# Mecabot_schematic.net
KiCad netlist of a schematic drawn in Altium Designer
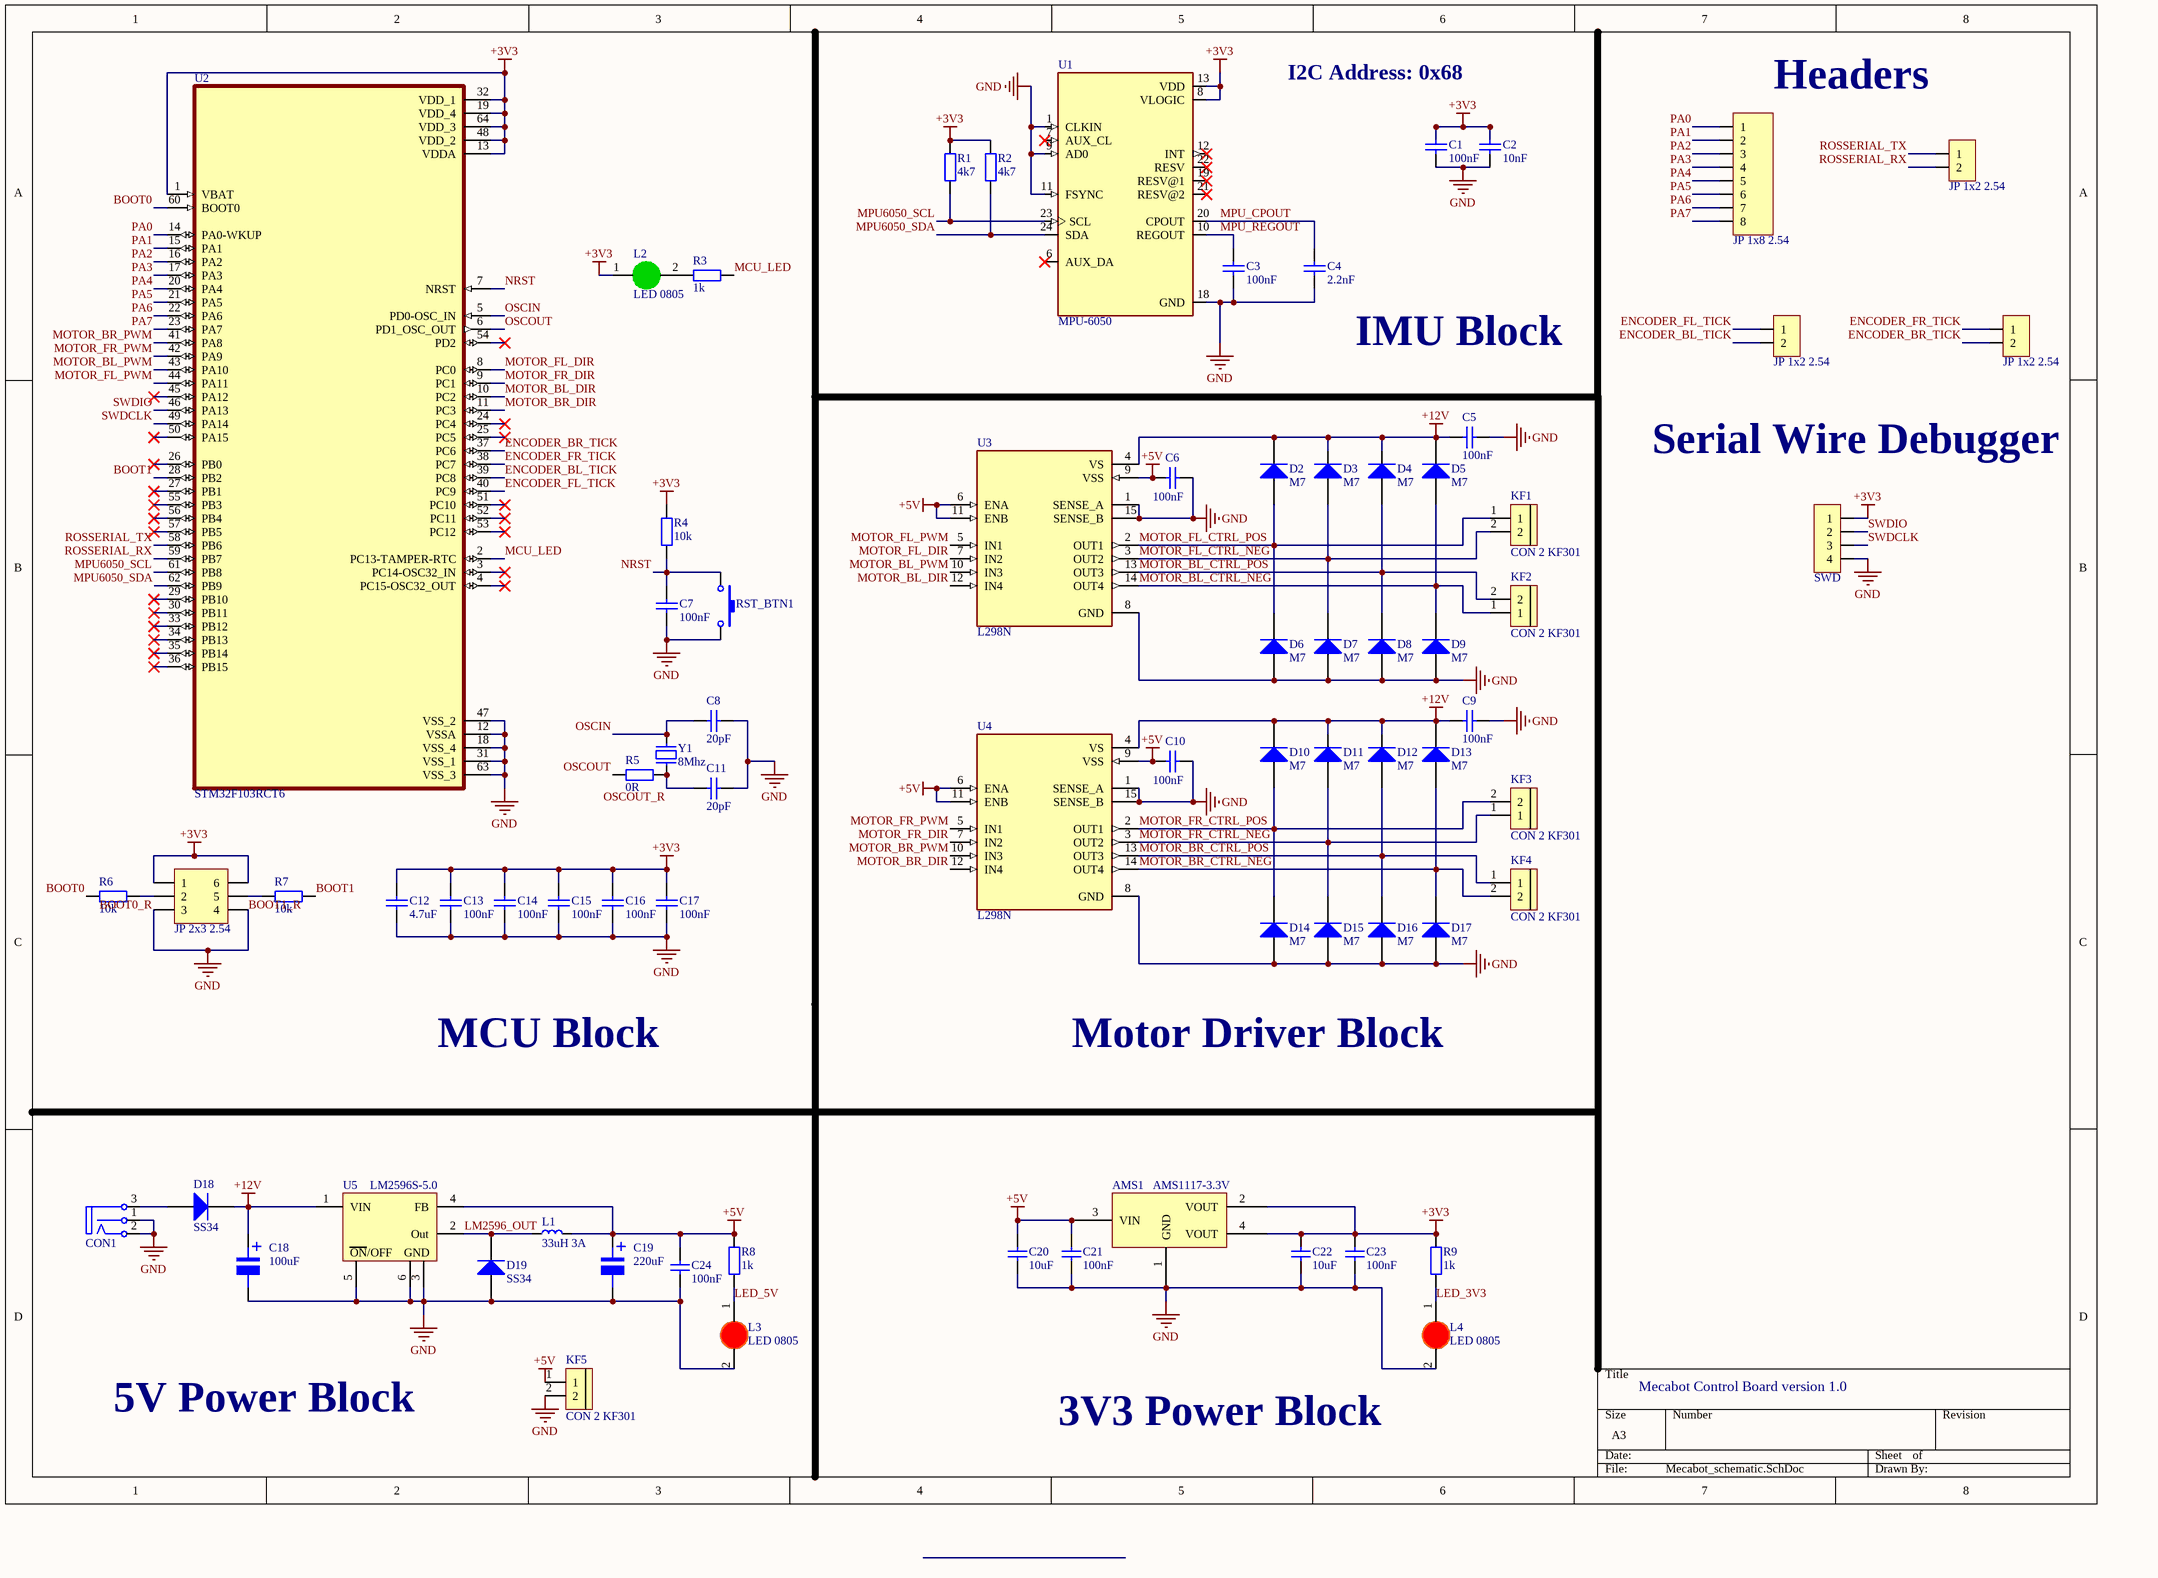
[diagram p0: Mecabot_schematic.SchDoc]

(export (version "E")
  (design (tool "Eeschema 10.0.6"))
  (components
    (comp (ref "AMS1")
      (value "AMS1117-3.3V")
      (footprint "SOT223")
      (description "Dán")
      (libsource (lib "Altium_Lib_by_KhueNguyenCreator") (part "AMS1117 SMD"))
    )
    (comp (ref "C1")
      (value "100nF")
      (footprint "tu 0603")
      (description "Dán")
      (libsource (lib "Altium_Lib_by_KhueNguyenCreator") (part "Tu 0603 104 50V 10%"))
    )
    (comp (ref "C2")
      (value "10nF")
      (footprint "tu 0603")
      (description "Dán")
      (libsource (lib "Altium_Lib_by_KhueNguyenCreator") (part "Tu 0603 103 50V 10%"))
    )
    (comp (ref "C3")
      (value "100nF")
      (footprint "tu 0603")
      (description "Dán")
      (libsource (lib "Altium_Lib_by_KhueNguyenCreator") (part "Tu 0603 104 50V 10%"))
    )
    (comp (ref "C4")
      (value "2.2nF")
      (footprint "tu 0603")
      (description "Dán")
      (libsource (lib "Altium_Lib_by_KhueNguyenCreator") (part "Tu 0603 22pF 50V 10%"))
    )
    (comp (ref "C5")
      (value "100nF")
      (footprint "tu 0603")
      (description "Dán")
      (libsource (lib "Altium_Lib_by_KhueNguyenCreator") (part "Tu 0603 104 50V 10%"))
    )
    (comp (ref "C6")
      (value "100nF")
      (footprint "tu 0603")
      (description "Dán")
      (libsource (lib "Altium_Lib_by_KhueNguyenCreator") (part "Tu 0603 104 50V 10%"))
    )
    (comp (ref "C7")
      (value "100nF")
      (footprint "tu 0603")
      (description "Dán")
      (libsource (lib "Altium_Lib_by_KhueNguyenCreator") (part "Tu 0603 104 50V 10%"))
    )
    (comp (ref "C8")
      (value "20pF")
      (footprint "tu 0603")
      (description "Dán")
      (libsource (lib "Altium_Lib_by_KhueNguyenCreator") (part "Tu 0603 104 50V 10%"))
    )
    (comp (ref "C9")
      (value "100nF")
      (footprint "tu 0603")
      (description "Dán")
      (libsource (lib "Altium_Lib_by_KhueNguyenCreator") (part "Tu 0603 104 50V 10%"))
    )
    (comp (ref "C10")
      (value "100nF")
      (footprint "tu 0603")
      (description "Dán")
      (libsource (lib "Altium_Lib_by_KhueNguyenCreator") (part "Tu 0603 104 50V 10%"))
    )
    (comp (ref "C11")
      (value "20pF")
      (footprint "tu 0603")
      (description "Dán")
      (libsource (lib "Altium_Lib_by_KhueNguyenCreator") (part "Tu 0603 104 50V 10%"))
    )
    (comp (ref "C12")
      (value "4.7uF")
      (footprint "tu 0805")
      (description "Dán")
      (libsource (lib "Altium_Lib_by_KhueNguyenCreator") (part "Tu 0805 475 25V 20%"))
    )
    (comp (ref "C13")
      (value "100nF")
      (footprint "tu 0603")
      (description "Dán")
      (libsource (lib "Altium_Lib_by_KhueNguyenCreator") (part "Tu 0603 104 50V 10%"))
    )
    (comp (ref "C14")
      (value "100nF")
      (footprint "tu 0603")
      (description "Dán")
      (libsource (lib "Altium_Lib_by_KhueNguyenCreator") (part "Tu 0603 104 50V 10%"))
    )
    (comp (ref "C15")
      (value "100nF")
      (footprint "tu 0603")
      (description "Dán")
      (libsource (lib "Altium_Lib_by_KhueNguyenCreator") (part "Tu 0603 104 50V 10%"))
    )
    (comp (ref "C16")
      (value "100nF")
      (footprint "tu 0603")
      (description "Dán")
      (libsource (lib "Altium_Lib_by_KhueNguyenCreator") (part "Tu 0603 104 50V 10%"))
    )
    (comp (ref "C17")
      (value "100nF")
      (footprint "tu 0603")
      (description "Dán")
      (libsource (lib "Altium_Lib_by_KhueNguyenCreator") (part "Tu 0603 104 50V 10%"))
    )
    (comp (ref "C18")
      (value "100uF")
      (footprint "tu nhom 8 (f)")
      (description "Dán")
      (libsource (lib "Altium_Lib_by_KhueNguyenCreator") (part "Tu Nhom 100uF 50V"))
    )
    (comp (ref "C19")
      (value "220uF")
      (footprint "tu nhom 8 (f)")
      (description "Dán")
      (libsource (lib "Altium_Lib_by_KhueNguyenCreator") (part "Tu Nhom 220uF 25V"))
    )
    (comp (ref "C20")
      (value "10uF")
      (footprint "C 0603")
      (description "Capacitor non-pol")
      (libsource (lib "chipfc_altium_libs") (part "Capacitor NP"))
    )
    (comp (ref "C21")
      (value "100nF")
      (footprint "C 0603")
      (description "Capacitor non-pol")
      (libsource (lib "chipfc_altium_libs") (part "Capacitor NP"))
    )
    (comp (ref "C22")
      (value "10uF")
      (footprint "C 0603")
      (description "Capacitor non-pol")
      (libsource (lib "chipfc_altium_libs") (part "Capacitor NP"))
    )
    (comp (ref "C23")
      (value "100nF")
      (footprint "C 0603")
      (description "Capacitor non-pol")
      (libsource (lib "chipfc_altium_libs") (part "Capacitor NP"))
    )
    (comp (ref "C24")
      (value "100nF")
      (footprint "C 0603")
      (description "Capacitor non-pol")
      (libsource (lib "chipfc_altium_libs") (part "Capacitor NP"))
    )
    (comp (ref "CON1")
      (value "CON DC PWR")
      (footprint "CONN/DC/PWR/5.0MM")
      (description "DC input connector")
      (libsource (lib "chipfc_altium_libs") (part "CON DC PWR"))
    )
    (comp (ref "D2")
      (value "M7")
      (footprint "DIODE SMA")
      (description "Dán")
      (libsource (lib "Altium_Lib_by_KhueNguyenCreator") (part "Diode M7 ( 4007 )"))
    )
    (comp (ref "D3")
      (value "M7")
      (footprint "DIODE SMA")
      (description "Dán")
      (libsource (lib "Altium_Lib_by_KhueNguyenCreator") (part "Diode M7 ( 4007 )"))
    )
    (comp (ref "D4")
      (value "M7")
      (footprint "DIODE SMA")
      (description "Dán")
      (libsource (lib "Altium_Lib_by_KhueNguyenCreator") (part "Diode M7 ( 4007 )"))
    )
    (comp (ref "D5")
      (value "M7")
      (footprint "DIODE SMA")
      (description "Dán")
      (libsource (lib "Altium_Lib_by_KhueNguyenCreator") (part "Diode M7 ( 4007 )"))
    )
    (comp (ref "D6")
      (value "M7")
      (footprint "DIODE SMA")
      (description "Dán")
      (libsource (lib "Altium_Lib_by_KhueNguyenCreator") (part "Diode M7 ( 4007 )"))
    )
    (comp (ref "D7")
      (value "M7")
      (footprint "DIODE SMA")
      (description "Dán")
      (libsource (lib "Altium_Lib_by_KhueNguyenCreator") (part "Diode M7 ( 4007 )"))
    )
    (comp (ref "D8")
      (value "M7")
      (footprint "DIODE SMA")
      (description "Dán")
      (libsource (lib "Altium_Lib_by_KhueNguyenCreator") (part "Diode M7 ( 4007 )"))
    )
    (comp (ref "D9")
      (value "M7")
      (footprint "DIODE SMA")
      (description "Dán")
      (libsource (lib "Altium_Lib_by_KhueNguyenCreator") (part "Diode M7 ( 4007 )"))
    )
    (comp (ref "D10")
      (value "M7")
      (footprint "DIODE SMA")
      (description "Dán")
      (libsource (lib "Altium_Lib_by_KhueNguyenCreator") (part "Diode M7 ( 4007 )"))
    )
    (comp (ref "D11")
      (value "M7")
      (footprint "DIODE SMA")
      (description "Dán")
      (libsource (lib "Altium_Lib_by_KhueNguyenCreator") (part "Diode M7 ( 4007 )"))
    )
    (comp (ref "D12")
      (value "M7")
      (footprint "DIODE SMA")
      (description "Dán")
      (libsource (lib "Altium_Lib_by_KhueNguyenCreator") (part "Diode M7 ( 4007 )"))
    )
    (comp (ref "D13")
      (value "M7")
      (footprint "DIODE SMA")
      (description "Dán")
      (libsource (lib "Altium_Lib_by_KhueNguyenCreator") (part "Diode M7 ( 4007 )"))
    )
    (comp (ref "D14")
      (value "M7")
      (footprint "DIODE SMA")
      (description "Dán")
      (libsource (lib "Altium_Lib_by_KhueNguyenCreator") (part "Diode M7 ( 4007 )"))
    )
    (comp (ref "D15")
      (value "M7")
      (footprint "DIODE SMA")
      (description "Dán")
      (libsource (lib "Altium_Lib_by_KhueNguyenCreator") (part "Diode M7 ( 4007 )"))
    )
    (comp (ref "D16")
      (value "M7")
      (footprint "DIODE SMA")
      (description "Dán")
      (libsource (lib "Altium_Lib_by_KhueNguyenCreator") (part "Diode M7 ( 4007 )"))
    )
    (comp (ref "D17")
      (value "M7")
      (footprint "DIODE SMA")
      (description "Dán")
      (libsource (lib "Altium_Lib_by_KhueNguyenCreator") (part "Diode M7 ( 4007 )"))
    )
    (comp (ref "D18")
      (value "SS34")
      (footprint "DIODE SMA")
      (description "Dán")
      (libsource (lib "Altium_Lib_by_KhueNguyenCreator") (part "Diode SS34 ( 1N5822 )"))
    )
    (comp (ref "D19")
      (value "SS34")
      (footprint "DIODE SMA")
      (description "Dán")
      (libsource (lib "Altium_Lib_by_KhueNguyenCreator") (part "Diode SS34 ( 1N5822 )"))
    )
    (comp (ref "JP1")
      (value "JP 1x8 2.54")
      (footprint "JP 1x8 CT")
      (description "Cắm")
      (libsource (lib "Altium_Lib_by_KhueNguyenCreator") (part "JP 1x8 2.54 Cai Thang"))
    )
    (comp (ref "JP2")
      (value "JP 1x2 2.54")
      (footprint "JP 1x2 DC")
      (description "Cắm")
      (libsource (lib "Altium_Lib_by_KhueNguyenCreator") (part "JP 1x2 2.54 Duc Cong"))
    )
    (comp (ref "JP3")
      (value "JP 1x2 2.54")
      (footprint "JP 1x2 DT")
      (description "Cắm")
      (libsource (lib "Altium_Lib_by_KhueNguyenCreator") (part "JP 1x2 2.54 Duc Thang"))
    )
    (comp (ref "JP4")
      (value "JP 1x2 2.54")
      (footprint "JP 1x2 DT")
      (description "Cắm")
      (libsource (lib "Altium_Lib_by_KhueNguyenCreator") (part "JP 1x2 2.54 Duc Thang"))
    )
    (comp (ref "JP5")
      (value "SWD")
      (footprint "JP 1x4 DC")
      (description "Cắm")
      (libsource (lib "Altium_Lib_by_KhueNguyenCreator") (part "JP 1x4 2.54 Duc Cong"))
    )
    (comp (ref "JP6")
      (value "JP 2x3 2.54")
      (footprint "JP 2x3 DT")
      (description "Cắm")
      (libsource (lib "Altium_Lib_by_KhueNguyenCreator") (part "JP 2x3 2.54 Duc Thang"))
    )
    (comp (ref "KF1")
      (value "CON 2 KF301")
      (footprint "Con 2 KF301 5.08")
      (description "Cắm")
      (libsource (lib "") (part "CON 2 KF301_1"))
    )
    (comp (ref "KF2")
      (value "CON 2 KF301")
      (footprint "Con 2 KF301 5.08")
      (description "Cắm")
      (libsource (lib "Altium_Lib_by_KhueNguyenCreator") (part "CON 2 KF301"))
    )
    (comp (ref "KF3")
      (value "CON 2 KF301")
      (footprint "Con 2 KF301 5.08")
      (description "Cắm")
      (libsource (lib "Altium_Lib_by_KhueNguyenCreator") (part "CON 2 KF301"))
    )
    (comp (ref "KF4")
      (value "CON 2 KF301")
      (footprint "Con 2 KF301 5.08")
      (description "Cắm")
      (libsource (lib "") (part "CON 2 KF301_1"))
    )
    (comp (ref "KF5")
      (value "CON 2 KF301")
      (footprint "Con 2 KF301 5.08")
      (description "Cắm")
      (libsource (lib "") (part "CON 2 KF301_1"))
    )
    (comp (ref "L1")
      (value "33uH 3A")
      (footprint "Inductor SMD 12x12x8")
      (description "Inductor")
      (libsource (lib "chipfc_altium_libs") (part "Inductor"))
    )
    (comp (ref "L2")
      (value "LED 0805")
      (footprint "LED-1206-Green")
      (description "Dán")
      (libsource (lib "Altium_Lib_by_KhueNguyenCreator") (part "LED 1206 Xanh La"))
    )
    (comp (ref "L3")
      (value "LED 0805")
      (footprint "LED-1206-Red")
      (description "Dán")
      (libsource (lib "Altium_Lib_by_KhueNguyenCreator") (part "LED 1206 Do"))
    )
    (comp (ref "L4")
      (value "LED 0805")
      (footprint "LED-1206-Red")
      (description "Dán")
      (libsource (lib "Altium_Lib_by_KhueNguyenCreator") (part "LED 1206 Do"))
    )
    (comp (ref "R1")
      (value "4k7")
      (footprint "tro smd 0603")
      (description "Dán")
      (libsource (lib "Altium_Lib_by_KhueNguyenCreator") (part "Tro 0603 1% 0R"))
    )
    (comp (ref "R2")
      (value "4k7")
      (footprint "tro smd 0603")
      (description "Dán")
      (libsource (lib "Altium_Lib_by_KhueNguyenCreator") (part "Tro 0603 1% 0R"))
    )
    (comp (ref "R3")
      (value "1k")
      (footprint "tro smd 0603")
      (description "Dán")
      (libsource (lib "Altium_Lib_by_KhueNguyenCreator") (part "Tro 0603 1% 0R"))
    )
    (comp (ref "R4")
      (value "10k")
      (footprint "tro smd 0603")
      (description "Dán")
      (libsource (lib "Altium_Lib_by_KhueNguyenCreator") (part "Tro 0603 1% 0R"))
    )
    (comp (ref "R5")
      (value "0R")
      (footprint "tro smd 0603")
      (description "Dán")
      (libsource (lib "Altium_Lib_by_KhueNguyenCreator") (part "Tro 0603 1% 0R"))
    )
    (comp (ref "R6")
      (value "10k")
      (footprint "tro smd 0603")
      (description "Dán")
      (libsource (lib "Altium_Lib_by_KhueNguyenCreator") (part "Tro 0603 1% 0R"))
    )
    (comp (ref "R7")
      (value "10k")
      (footprint "tro smd 0603")
      (description "Dán")
      (libsource (lib "Altium_Lib_by_KhueNguyenCreator") (part "Tro 0603 1% 0R"))
    )
    (comp (ref "R8")
      (value "1k")
      (footprint "tro smd 0603")
      (description "Dán")
      (libsource (lib "Altium_Lib_by_KhueNguyenCreator") (part "Tro 0603 1% 0R"))
    )
    (comp (ref "R9")
      (value "1k")
      (footprint "tro smd 0603")
      (description "Dán")
      (libsource (lib "Altium_Lib_by_KhueNguyenCreator") (part "Tro 0603 1% 0R"))
    )
    (comp (ref "RST_BTN1")
      (value "Nut Nhan 2 Chan SMD 3x6x2.5")
      (footprint "Nut Nhan 2 Chan SMD 3x6x2.5")
      (libsource (lib "Altium_Lib_by_KhueNguyenCreator") (part "Nut Nhan 2 Chan SMD 3x6x2.5"))
    )
    (comp (ref "U1")
      (value "MPU-6050")
      (footprint "QFN50P400X400X95-24N")
      (description "MPU-6050 series Accelerometer, Gyroscope, 3 Axis Sensor Evaluation Board")
      (fields (field (name "MF") "TDK InvenSense"))
      (libsource (lib "MPU-6050") (part "MPU-6050"))
    )
    (comp (ref "U2")
      (value "STM32F103RCT6")
      (footprint "QFP50P1200X1200X160-64N")
      (description "ARMÂ® CortexÂ®-M3 STM32F1 Microcontroller IC 32-Bit 72MHz 256KB (256K x 8) FLASH 64-LQFP (10x10)")
      (fields (field (name "MF") "STMicroelectronics"))
      (libsource (lib "STM32F103RCT6") (part "STM32F103RCT6"))
    )
    (comp (ref "U3")
      (value "L298N")
      (footprint "L298N")
      (description "Half Bridge _4_ Driver DC Motors, Relays, Solenoids, Stepper Motors Bipolar 15-Multiwatt")
      (fields (field (name "MF") "STMicroelectronics"))
      (libsource (lib "Altium_Lib_by_KhueNguyenCreator") (part "L298N"))
    )
    (comp (ref "U4")
      (value "L298N")
      (footprint "L298N")
      (description "Half Bridge _4_ Driver DC Motors, Relays, Solenoids, Stepper Motors Bipolar 15-Multiwatt")
      (fields (field (name "MF") "STMicroelectronics"))
      (libsource (lib "Altium_Lib_by_KhueNguyenCreator") (part "L298N"))
    )
    (comp (ref "U5")
      (value "LM2596S-5.0")
      (footprint "TO-263-5")
      (description "Simple Switcher 3A Step-Down Voltage Regulator")
      (libsource (lib "chipfc_altium_libs") (part "LM2596S-5.0"))
    )
    (comp (ref "Y1")
      (value "8Mhz")
      (footprint "Thach Anh 2 chan cam")
      (description "Crystal For all Crystal 2pin.")
      (libsource (lib "Altium_Lib_by_KhueNguyenCreator") (part "Thach Anh 2 chan Cam"))
    )
  )
  (nets
    (net (code "1") (name "+3V3") (class "Default")
      (node (ref "AMS1") (pin "2") (pinfunction "VOUT_2") (pintype "passive"))
      (node (ref "AMS1") (pin "4") (pinfunction "VOUT_4") (pintype "passive"))
      (node (ref "C1") (pin "1") (pinfunction "1_1") (pintype "passive"))
      (node (ref "C12") (pin "1") (pinfunction "1_1") (pintype "passive"))
      (node (ref "C13") (pin "1") (pinfunction "1_1") (pintype "passive"))
      (node (ref "C14") (pin "1") (pinfunction "1_1") (pintype "passive"))
      (node (ref "C15") (pin "1") (pinfunction "1_1") (pintype "passive"))
      (node (ref "C16") (pin "1") (pinfunction "1_1") (pintype "passive"))
      (node (ref "C17") (pin "1") (pinfunction "1_1") (pintype "passive"))
      (node (ref "C2") (pin "1") (pinfunction "1_1") (pintype "passive"))
      (node (ref "C22") (pin "1") (pinfunction "1_1") (pintype "passive"))
      (node (ref "C23") (pin "1") (pinfunction "1_1") (pintype "passive"))
      (node (ref "JP5") (pin "1") (pinfunction "1_1") (pintype "passive"))
      (node (ref "JP6") (pin "1") (pinfunction "1_1") (pintype "passive"))
      (node (ref "JP6") (pin "6") (pinfunction "6_6") (pintype "passive"))
      (node (ref "L2") (pin "1") (pinfunction "A_1") (pintype "passive"))
      (node (ref "R1") (pin "1") (pinfunction "1_1") (pintype "passive"))
      (node (ref "R2") (pin "1") (pinfunction "1_1") (pintype "passive"))
      (node (ref "R4") (pin "1") (pinfunction "1_1") (pintype "passive"))
      (node (ref "R9") (pin "2") (pinfunction "2_2") (pintype "passive"))
      (node (ref "U1") (pin "13") (pinfunction "VDD_13") (pintype "power_in"))
      (node (ref "U1") (pin "8") (pinfunction "VLOGIC_8") (pintype "power_in"))
      (node (ref "U2") (pin "1") (pinfunction "VBAT_1") (pintype "input"))
      (node (ref "U2") (pin "13") (pinfunction "VDDA_13") (pintype "power_in"))
      (node (ref "U2") (pin "19") (pinfunction "VDD_4_19") (pintype "power_in"))
      (node (ref "U2") (pin "32") (pinfunction "VDD_1_32") (pintype "power_in"))
      (node (ref "U2") (pin "48") (pinfunction "VDD_2_48") (pintype "power_in"))
      (node (ref "U2") (pin "64") (pinfunction "VDD_3_64") (pintype "power_in"))
    )
    (net (code "2") (name "+5V") (class "Default")
      (node (ref "AMS1") (pin "3") (pinfunction "VIN_3") (pintype "passive"))
      (node (ref "C10") (pin "1") (pinfunction "1_1") (pintype "passive"))
      (node (ref "C19") (pin "1") (pinfunction "1_1") (pintype "passive"))
      (node (ref "C20") (pin "1") (pinfunction "1_1") (pintype "passive"))
      (node (ref "C21") (pin "1") (pinfunction "1_1") (pintype "passive"))
      (node (ref "C24") (pin "1") (pinfunction "1_1") (pintype "passive"))
      (node (ref "C6") (pin "1") (pinfunction "1_1") (pintype "passive"))
      (node (ref "KF5") (pin "1") (pinfunction "1_1") (pintype "passive"))
      (node (ref "L1") (pin "2") (pinfunction "2_2") (pintype "passive"))
      (node (ref "R8") (pin "2") (pinfunction "2_2") (pintype "passive"))
      (node (ref "U3") (pin "11") (pinfunction "ENB_11") (pintype "input"))
      (node (ref "U3") (pin "6") (pinfunction "ENA_6") (pintype "input"))
      (node (ref "U3") (pin "9") (pinfunction "VSS_9") (pintype "input"))
      (node (ref "U4") (pin "11") (pinfunction "ENB_11") (pintype "input"))
      (node (ref "U4") (pin "6") (pinfunction "ENA_6") (pintype "input"))
      (node (ref "U4") (pin "9") (pinfunction "VSS_9") (pintype "input"))
      (node (ref "U5") (pin "4") (pinfunction "FB_4") (pintype "passive"))
    )
    (net (code "3") (name "+12V") (class "Default")
      (node (ref "C18") (pin "1") (pinfunction "1_1") (pintype "passive"))
      (node (ref "C5") (pin "1") (pinfunction "1_1") (pintype "passive"))
      (node (ref "C9") (pin "1") (pinfunction "1_1") (pintype "passive"))
      (node (ref "D10") (pin "2") (pinfunction "K_2") (pintype "passive"))
      (node (ref "D11") (pin "2") (pinfunction "K_2") (pintype "passive"))
      (node (ref "D12") (pin "2") (pinfunction "K_2") (pintype "passive"))
      (node (ref "D13") (pin "2") (pinfunction "K_2") (pintype "passive"))
      (node (ref "D18") (pin "2") (pinfunction "K_2") (pintype "passive"))
      (node (ref "D2") (pin "2") (pinfunction "K_2") (pintype "passive"))
      (node (ref "D3") (pin "2") (pinfunction "K_2") (pintype "passive"))
      (node (ref "D4") (pin "2") (pinfunction "K_2") (pintype "passive"))
      (node (ref "D5") (pin "2") (pinfunction "K_2") (pintype "passive"))
      (node (ref "U3") (pin "4") (pinfunction "VS_4") (pintype "power_in"))
      (node (ref "U4") (pin "4") (pinfunction "VS_4") (pintype "power_in"))
      (node (ref "U5") (pin "1") (pinfunction "VIN_1") (pintype "passive"))
    )
    (net (code "4") (name "/BOOT0") (class "Default")
      (node (ref "R6") (pin "2") (pinfunction "2_2") (pintype "passive"))
      (node (ref "U2") (pin "60") (pinfunction "BOOT0_60") (pintype "input"))
    )
    (net (code "5") (name "/BOOT0_R") (class "Default")
      (node (ref "JP6") (pin "2") (pinfunction "2_2") (pintype "passive"))
      (node (ref "R6") (pin "1") (pinfunction "1_1") (pintype "passive"))
    )
    (net (code "6") (name "/BOOT1") (class "Default")
      (node (ref "R7") (pin "1") (pinfunction "1_1") (pintype "passive"))
      (node (ref "U2") (pin "28") (pinfunction "PB2_28") (pintype "bidirectional"))
    )
    (net (code "7") (name "/BOOT1_R") (class "Default")
      (node (ref "JP6") (pin "5") (pinfunction "5_5") (pintype "passive"))
      (node (ref "R7") (pin "2") (pinfunction "2_2") (pintype "passive"))
    )
    (net (code "8") (name "/ENCODER_BL_TICK") (class "Default")
      (node (ref "JP3") (pin "2") (pinfunction "2_2") (pintype "passive"))
      (node (ref "U2") (pin "39") (pinfunction "PC8_39") (pintype "bidirectional"))
    )
    (net (code "9") (name "/ENCODER_BR_TICK") (class "Default")
      (node (ref "JP4") (pin "2") (pinfunction "2_2") (pintype "passive"))
      (node (ref "U2") (pin "37") (pinfunction "PC6_37") (pintype "bidirectional"))
    )
    (net (code "10") (name "/ENCODER_FL_TICK") (class "Default")
      (node (ref "JP3") (pin "1") (pinfunction "1_1") (pintype "passive"))
      (node (ref "U2") (pin "40") (pinfunction "PC9_40") (pintype "bidirectional"))
    )
    (net (code "11") (name "/ENCODER_FR_TICK") (class "Default")
      (node (ref "JP4") (pin "1") (pinfunction "1_1") (pintype "passive"))
      (node (ref "U2") (pin "38") (pinfunction "PC7_38") (pintype "bidirectional"))
    )
    (net (code "12") (name "/LED_3V3") (class "Default")
      (node (ref "L4") (pin "1") (pinfunction "A_1") (pintype "passive"))
      (node (ref "R9") (pin "1") (pinfunction "1_1") (pintype "passive"))
    )
    (net (code "13") (name "/LED_5V") (class "Default")
      (node (ref "L3") (pin "1") (pinfunction "A_1") (pintype "passive"))
      (node (ref "R8") (pin "1") (pinfunction "1_1") (pintype "passive"))
    )
    (net (code "14") (name "/LM2596_OUT") (class "Default")
      (node (ref "D19") (pin "2") (pinfunction "K_2") (pintype "passive"))
      (node (ref "L1") (pin "1") (pinfunction "1_1") (pintype "passive"))
      (node (ref "U5") (pin "2") (pinfunction "Out_2") (pintype "passive"))
    )
    (net (code "15") (name "/MCU_LED") (class "Default")
      (node (ref "R3") (pin "1") (pinfunction "1_1") (pintype "passive"))
      (node (ref "U2") (pin "2") (pinfunction "PC13-TAMPER-RTC_2") (pintype "bidirectional"))
    )
    (net (code "16") (name "/MOTOR_BL_CTRL_NEG") (class "Default")
      (node (ref "D5") (pin "1") (pinfunction "A_1") (pintype "passive"))
      (node (ref "D9") (pin "2") (pinfunction "K_2") (pintype "passive"))
      (node (ref "KF2") (pin "1") (pinfunction "1_1") (pintype "passive"))
      (node (ref "U3") (pin "14") (pinfunction "OUT4_14") (pintype "output"))
    )
    (net (code "17") (name "/MOTOR_BL_CTRL_POS") (class "Default")
      (node (ref "D4") (pin "1") (pinfunction "A_1") (pintype "passive"))
      (node (ref "D8") (pin "2") (pinfunction "K_2") (pintype "passive"))
      (node (ref "KF2") (pin "2") (pinfunction "2_2") (pintype "passive"))
      (node (ref "U3") (pin "13") (pinfunction "OUT3_13") (pintype "output"))
    )
    (net (code "18") (name "/MOTOR_BL_DIR") (class "Default")
      (node (ref "U2") (pin "10") (pinfunction "PC2_10") (pintype "bidirectional"))
      (node (ref "U3") (pin "12") (pinfunction "IN4_12") (pintype "input"))
    )
    (net (code "19") (name "/MOTOR_BL_PWM") (class "Default")
      (node (ref "U2") (pin "43") (pinfunction "PA10_43") (pintype "bidirectional"))
      (node (ref "U3") (pin "10") (pinfunction "IN3_10") (pintype "input"))
    )
    (net (code "20") (name "/MOTOR_BR_CTRL_NEG") (class "Default")
      (node (ref "D13") (pin "1") (pinfunction "A_1") (pintype "passive"))
      (node (ref "D17") (pin "2") (pinfunction "K_2") (pintype "passive"))
      (node (ref "KF4") (pin "2") (pinfunction "2_2") (pintype "passive"))
      (node (ref "U4") (pin "14") (pinfunction "OUT4_14") (pintype "output"))
    )
    (net (code "21") (name "/MOTOR_BR_CTRL_POS") (class "Default")
      (node (ref "D12") (pin "1") (pinfunction "A_1") (pintype "passive"))
      (node (ref "D16") (pin "2") (pinfunction "K_2") (pintype "passive"))
      (node (ref "KF4") (pin "1") (pinfunction "1_1") (pintype "passive"))
      (node (ref "U4") (pin "13") (pinfunction "OUT3_13") (pintype "output"))
    )
    (net (code "22") (name "/MOTOR_BR_DIR") (class "Default")
      (node (ref "U2") (pin "11") (pinfunction "PC3_11") (pintype "bidirectional"))
      (node (ref "U4") (pin "12") (pinfunction "IN4_12") (pintype "input"))
    )
    (net (code "23") (name "/MOTOR_BR_PWM") (class "Default")
      (node (ref "U2") (pin "41") (pinfunction "PA8_41") (pintype "bidirectional"))
      (node (ref "U4") (pin "10") (pinfunction "IN3_10") (pintype "input"))
    )
    (net (code "24") (name "/MOTOR_FL_CTRL_NEG") (class "Default")
      (node (ref "D3") (pin "1") (pinfunction "A_1") (pintype "passive"))
      (node (ref "D7") (pin "2") (pinfunction "K_2") (pintype "passive"))
      (node (ref "KF1") (pin "2") (pinfunction "2_2") (pintype "passive"))
      (node (ref "U3") (pin "3") (pinfunction "OUT2_3") (pintype "output"))
    )
    (net (code "25") (name "/MOTOR_FL_CTRL_POS") (class "Default")
      (node (ref "D2") (pin "1") (pinfunction "A_1") (pintype "passive"))
      (node (ref "D6") (pin "2") (pinfunction "K_2") (pintype "passive"))
      (node (ref "KF1") (pin "1") (pinfunction "1_1") (pintype "passive"))
      (node (ref "U3") (pin "2") (pinfunction "OUT1_2") (pintype "output"))
    )
    (net (code "26") (name "/MOTOR_FL_DIR") (class "Default")
      (node (ref "U2") (pin "8") (pinfunction "PC0_8") (pintype "bidirectional"))
      (node (ref "U3") (pin "7") (pinfunction "IN2_7") (pintype "input"))
    )
    (net (code "27") (name "/MOTOR_FL_PWM") (class "Default")
      (node (ref "U2") (pin "44") (pinfunction "PA11_44") (pintype "bidirectional"))
      (node (ref "U3") (pin "5") (pinfunction "IN1_5") (pintype "input"))
    )
    (net (code "28") (name "/MOTOR_FR_CTRL_NEG") (class "Default")
      (node (ref "D11") (pin "1") (pinfunction "A_1") (pintype "passive"))
      (node (ref "D15") (pin "2") (pinfunction "K_2") (pintype "passive"))
      (node (ref "KF3") (pin "1") (pinfunction "1_1") (pintype "passive"))
      (node (ref "U4") (pin "3") (pinfunction "OUT2_3") (pintype "output"))
    )
    (net (code "29") (name "/MOTOR_FR_CTRL_POS") (class "Default")
      (node (ref "D10") (pin "1") (pinfunction "A_1") (pintype "passive"))
      (node (ref "D14") (pin "2") (pinfunction "K_2") (pintype "passive"))
      (node (ref "KF3") (pin "2") (pinfunction "2_2") (pintype "passive"))
      (node (ref "U4") (pin "2") (pinfunction "OUT1_2") (pintype "output"))
    )
    (net (code "30") (name "/MOTOR_FR_DIR") (class "Default")
      (node (ref "U2") (pin "9") (pinfunction "PC1_9") (pintype "bidirectional"))
      (node (ref "U4") (pin "7") (pinfunction "IN2_7") (pintype "input"))
    )
    (net (code "31") (name "/MOTOR_FR_PWM") (class "Default")
      (node (ref "U2") (pin "42") (pinfunction "PA9_42") (pintype "bidirectional"))
      (node (ref "U4") (pin "5") (pinfunction "IN1_5") (pintype "input"))
    )
    (net (code "32") (name "/MPU6050_SCL") (class "Default")
      (node (ref "R1") (pin "2") (pinfunction "2_2") (pintype "passive"))
      (node (ref "U1") (pin "23") (pinfunction "SCL_23") (pintype "input"))
      (node (ref "U2") (pin "61") (pinfunction "PB8_61") (pintype "bidirectional"))
    )
    (net (code "33") (name "/MPU6050_SDA") (class "Default")
      (node (ref "R2") (pin "2") (pinfunction "2_2") (pintype "passive"))
      (node (ref "U1") (pin "24") (pinfunction "SDA_24") (pintype "bidirectional"))
      (node (ref "U2") (pin "62") (pinfunction "PB9_62") (pintype "bidirectional"))
    )
    (net (code "34") (name "/MPU_CPOUT") (class "Default")
      (node (ref "C4") (pin "2") (pinfunction "2_2") (pintype "passive"))
      (node (ref "U1") (pin "20") (pinfunction "CPOUT_20") (pintype "passive"))
    )
    (net (code "35") (name "/MPU_REGOUT") (class "Default")
      (node (ref "C3") (pin "1") (pinfunction "1_1") (pintype "passive"))
      (node (ref "U1") (pin "10") (pinfunction "REGOUT_10") (pintype "passive"))
    )
    (net (code "36") (name "/NRST") (class "Default")
      (node (ref "C7") (pin "1") (pinfunction "1_1") (pintype "passive"))
      (node (ref "R4") (pin "2") (pinfunction "2_2") (pintype "passive"))
      (node (ref "RST_BTN1") (pin "1") (pinfunction "1_1") (pintype "passive"))
      (node (ref "U2") (pin "7") (pinfunction "NRST_7") (pintype "input"))
    )
    (net (code "37") (name "/OSCIN") (class "Default")
      (node (ref "C8") (pin "2") (pinfunction "2_2") (pintype "passive"))
      (node (ref "U2") (pin "5") (pinfunction "PD0-OSC_IN_5") (pintype "input"))
      (node (ref "Y1") (pin "1") (pinfunction "1_1") (pintype "passive"))
    )
    (net (code "38") (name "/OSCOUT") (class "Default")
      (node (ref "R5") (pin "2") (pinfunction "2_2") (pintype "passive"))
      (node (ref "U2") (pin "6") (pinfunction "PD1_OSC_OUT_6") (pintype "output"))
    )
    (net (code "39") (name "/OSCOUT_R") (class "Default")
      (node (ref "C11") (pin "2") (pinfunction "2_2") (pintype "passive"))
      (node (ref "R5") (pin "1") (pinfunction "1_1") (pintype "passive"))
      (node (ref "Y1") (pin "2") (pinfunction "2_2") (pintype "passive"))
    )
    (net (code "40") (name "/PA0") (class "Default")
      (node (ref "JP1") (pin "1") (pinfunction "1_1") (pintype "passive"))
      (node (ref "U2") (pin "14") (pinfunction "PA0-WKUP_14") (pintype "bidirectional"))
    )
    (net (code "41") (name "/PA1") (class "Default")
      (node (ref "JP1") (pin "2") (pinfunction "2_2") (pintype "passive"))
      (node (ref "U2") (pin "15") (pinfunction "PA1_15") (pintype "bidirectional"))
    )
    (net (code "42") (name "/PA2") (class "Default")
      (node (ref "JP1") (pin "3") (pinfunction "3_3") (pintype "passive"))
      (node (ref "U2") (pin "16") (pinfunction "PA2_16") (pintype "bidirectional"))
    )
    (net (code "43") (name "/PA3") (class "Default")
      (node (ref "JP1") (pin "4") (pinfunction "4_4") (pintype "passive"))
      (node (ref "U2") (pin "17") (pinfunction "PA3_17") (pintype "bidirectional"))
    )
    (net (code "44") (name "/PA4") (class "Default")
      (node (ref "JP1") (pin "5") (pinfunction "5_5") (pintype "passive"))
      (node (ref "U2") (pin "20") (pinfunction "PA4_20") (pintype "bidirectional"))
    )
    (net (code "45") (name "/PA5") (class "Default")
      (node (ref "JP1") (pin "6") (pinfunction "6_6") (pintype "passive"))
      (node (ref "U2") (pin "21") (pinfunction "PA5_21") (pintype "bidirectional"))
    )
    (net (code "46") (name "/PA6") (class "Default")
      (node (ref "JP1") (pin "7") (pinfunction "7_7") (pintype "passive"))
      (node (ref "U2") (pin "22") (pinfunction "PA6_22") (pintype "bidirectional"))
    )
    (net (code "47") (name "/PA7") (class "Default")
      (node (ref "JP1") (pin "8") (pinfunction "8_8") (pintype "passive"))
      (node (ref "U2") (pin "23") (pinfunction "PA7_23") (pintype "bidirectional"))
    )
    (net (code "48") (name "/ROSSERIAL_RX") (class "Default")
      (node (ref "JP2") (pin "2") (pinfunction "2_2") (pintype "passive"))
      (node (ref "U2") (pin "59") (pinfunction "PB7_59") (pintype "bidirectional"))
    )
    (net (code "49") (name "/ROSSERIAL_TX") (class "Default")
      (node (ref "JP2") (pin "1") (pinfunction "1_1") (pintype "passive"))
      (node (ref "U2") (pin "58") (pinfunction "PB6_58") (pintype "bidirectional"))
    )
    (net (code "50") (name "/SWDCLK") (class "Default")
      (node (ref "JP5") (pin "3") (pinfunction "3_3") (pintype "passive"))
      (node (ref "U2") (pin "49") (pinfunction "PA14_49") (pintype "bidirectional"))
    )
    (net (code "51") (name "/SWDIO") (class "Default")
      (node (ref "JP5") (pin "2") (pinfunction "2_2") (pintype "passive"))
      (node (ref "U2") (pin "46") (pinfunction "PA13_46") (pintype "bidirectional"))
    )
    (net (code "52") (name "GND") (class "Default")
      (node (ref "AMS1") (pin "1") (pinfunction "GND_1") (pintype "passive"))
      (node (ref "C1") (pin "2") (pinfunction "2_2") (pintype "passive"))
      (node (ref "C10") (pin "2") (pinfunction "2_2") (pintype "passive"))
      (node (ref "C11") (pin "1") (pinfunction "1_1") (pintype "passive"))
      (node (ref "C12") (pin "2") (pinfunction "2_2") (pintype "passive"))
      (node (ref "C13") (pin "2") (pinfunction "2_2") (pintype "passive"))
      (node (ref "C14") (pin "2") (pinfunction "2_2") (pintype "passive"))
      (node (ref "C15") (pin "2") (pinfunction "2_2") (pintype "passive"))
      (node (ref "C16") (pin "2") (pinfunction "2_2") (pintype "passive"))
      (node (ref "C17") (pin "2") (pinfunction "2_2") (pintype "passive"))
      (node (ref "C18") (pin "2") (pinfunction "2_2") (pintype "passive"))
      (node (ref "C19") (pin "2") (pinfunction "2_2") (pintype "passive"))
      (node (ref "C2") (pin "2") (pinfunction "2_2") (pintype "passive"))
      (node (ref "C20") (pin "2") (pinfunction "2_2") (pintype "passive"))
      (node (ref "C21") (pin "2") (pinfunction "2_2") (pintype "passive"))
      (node (ref "C22") (pin "2") (pinfunction "2_2") (pintype "passive"))
      (node (ref "C23") (pin "2") (pinfunction "2_2") (pintype "passive"))
      (node (ref "C24") (pin "2") (pinfunction "2_2") (pintype "passive"))
      (node (ref "C3") (pin "2") (pinfunction "2_2") (pintype "passive"))
      (node (ref "C4") (pin "1") (pinfunction "1_1") (pintype "passive"))
      (node (ref "C5") (pin "2") (pinfunction "2_2") (pintype "passive"))
      (node (ref "C6") (pin "2") (pinfunction "2_2") (pintype "passive"))
      (node (ref "C7") (pin "2") (pinfunction "2_2") (pintype "passive"))
      (node (ref "C8") (pin "1") (pinfunction "1_1") (pintype "passive"))
      (node (ref "C9") (pin "2") (pinfunction "2_2") (pintype "passive"))
      (node (ref "CON1") (pin "1") (pinfunction "S_1") (pintype "power_in"))
      (node (ref "CON1") (pin "2") (pinfunction "T_2") (pintype "passive"))
      (node (ref "D14") (pin "1") (pinfunction "A_1") (pintype "passive"))
      (node (ref "D15") (pin "1") (pinfunction "A_1") (pintype "passive"))
      (node (ref "D16") (pin "1") (pinfunction "A_1") (pintype "passive"))
      (node (ref "D17") (pin "1") (pinfunction "A_1") (pintype "passive"))
      (node (ref "D19") (pin "1") (pinfunction "A_1") (pintype "passive"))
      (node (ref "D6") (pin "1") (pinfunction "A_1") (pintype "passive"))
      (node (ref "D7") (pin "1") (pinfunction "A_1") (pintype "passive"))
      (node (ref "D8") (pin "1") (pinfunction "A_1") (pintype "passive"))
      (node (ref "D9") (pin "1") (pinfunction "A_1") (pintype "passive"))
      (node (ref "JP5") (pin "4") (pinfunction "4_4") (pintype "passive"))
      (node (ref "JP6") (pin "3") (pinfunction "3_3") (pintype "passive"))
      (node (ref "JP6") (pin "4") (pinfunction "4_4") (pintype "passive"))
      (node (ref "KF5") (pin "2") (pinfunction "2_2") (pintype "passive"))
      (node (ref "L3") (pin "2") (pinfunction "K_2") (pintype "passive"))
      (node (ref "L4") (pin "2") (pinfunction "K_2") (pintype "passive"))
      (node (ref "RST_BTN1") (pin "2") (pinfunction "2_2") (pintype "passive"))
      (node (ref "U1") (pin "1") (pinfunction "CLKIN_1") (pintype "input"))
      (node (ref "U1") (pin "11") (pinfunction "FSYNC_11") (pintype "input"))
      (node (ref "U1") (pin "18") (pinfunction "GND_18") (pintype "power_in"))
      (node (ref "U1") (pin "9") (pinfunction "AD0_9") (pintype "input"))
      (node (ref "U2") (pin "12") (pinfunction "VSSA_12") (pintype "power_in"))
      (node (ref "U2") (pin "18") (pinfunction "VSS_4_18") (pintype "power_in"))
      (node (ref "U2") (pin "31") (pinfunction "VSS_1_31") (pintype "power_in"))
      (node (ref "U2") (pin "47") (pinfunction "VSS_2_47") (pintype "power_in"))
      (node (ref "U2") (pin "63") (pinfunction "VSS_3_63") (pintype "power_in"))
      (node (ref "U3") (pin "1") (pinfunction "SENSE_A_1") (pintype "passive"))
      (node (ref "U3") (pin "15") (pinfunction "SENSE_B_15") (pintype "passive"))
      (node (ref "U3") (pin "8") (pinfunction "GND_8") (pintype "power_in"))
      (node (ref "U4") (pin "1") (pinfunction "SENSE_A_1") (pintype "passive"))
      (node (ref "U4") (pin "15") (pinfunction "SENSE_B_15") (pintype "passive"))
      (node (ref "U4") (pin "8") (pinfunction "GND_8") (pintype "power_in"))
      (node (ref "U5") (pin "3") (pinfunction "GND_3") (pintype "passive"))
      (node (ref "U5") (pin "5") (pinfunction "~{ON}/OFF_5") (pintype "passive"))
      (node (ref "U5") (pin "6") (pinfunction "PAD_6") (pintype "passive"))
    )
    (net (code "53") (name "Net-(CON1-TN)") (class "Default")
      (node (ref "CON1") (pin "3") (pinfunction "TN_3") (pintype "passive"))
      (node (ref "D18") (pin "1") (pinfunction "A_1") (pintype "passive"))
    )
    (net (code "54") (name "Net-(L2-K)") (class "Default")
      (node (ref "L2") (pin "2") (pinfunction "K_2") (pintype "passive"))
      (node (ref "R3") (pin "2") (pinfunction "2_2") (pintype "passive"))
    )
    (net (code "55") (name "unconnected-(U1-AUX_CL-Pad7)") (class "Default")
      (node (ref "U1") (pin "7") (pinfunction "AUX_CL_7") (pintype "input+no_connect"))
    )
    (net (code "56") (name "unconnected-(U1-AUX_DA-Pad6)") (class "Default")
      (node (ref "U1") (pin "6") (pinfunction "AUX_DA_6") (pintype "bidirectional+no_connect"))
    )
    (net (code "57") (name "unconnected-(U1-INT-Pad12)") (class "Default")
      (node (ref "U1") (pin "12") (pinfunction "INT_12") (pintype "output+no_connect"))
    )
    (net (code "58") (name "unconnected-(U1-RESV-Pad22)") (class "Default")
      (node (ref "U1") (pin "22") (pinfunction "RESV_22") (pintype "passive+no_connect"))
    )
    (net (code "59") (name "unconnected-(U1-RESV@1-Pad19)") (class "Default")
      (node (ref "U1") (pin "19") (pinfunction "RESV@1_19") (pintype "passive+no_connect"))
    )
    (net (code "60") (name "unconnected-(U1-RESV@2-Pad21)") (class "Default")
      (node (ref "U1") (pin "21") (pinfunction "RESV@2_21") (pintype "passive+no_connect"))
    )
    (net (code "61") (name "unconnected-(U2-PA12-Pad45)") (class "Default")
      (node (ref "U2") (pin "45") (pinfunction "PA12_45") (pintype "bidirectional+no_connect"))
    )
    (net (code "62") (name "unconnected-(U2-PA15-Pad50)") (class "Default")
      (node (ref "U2") (pin "50") (pinfunction "PA15_50") (pintype "bidirectional+no_connect"))
    )
    (net (code "63") (name "unconnected-(U2-PB0-Pad26)") (class "Default")
      (node (ref "U2") (pin "26") (pinfunction "PB0_26") (pintype "bidirectional+no_connect"))
    )
    (net (code "64") (name "unconnected-(U2-PB1-Pad27)") (class "Default")
      (node (ref "U2") (pin "27") (pinfunction "PB1_27") (pintype "bidirectional+no_connect"))
    )
    (net (code "65") (name "unconnected-(U2-PB3-Pad55)") (class "Default")
      (node (ref "U2") (pin "55") (pinfunction "PB3_55") (pintype "bidirectional+no_connect"))
    )
    (net (code "66") (name "unconnected-(U2-PB4-Pad56)") (class "Default")
      (node (ref "U2") (pin "56") (pinfunction "PB4_56") (pintype "bidirectional+no_connect"))
    )
    (net (code "67") (name "unconnected-(U2-PB5-Pad57)") (class "Default")
      (node (ref "U2") (pin "57") (pinfunction "PB5_57") (pintype "bidirectional+no_connect"))
    )
    (net (code "68") (name "unconnected-(U2-PB10-Pad29)") (class "Default")
      (node (ref "U2") (pin "29") (pinfunction "PB10_29") (pintype "bidirectional+no_connect"))
    )
    (net (code "69") (name "unconnected-(U2-PB11-Pad30)") (class "Default")
      (node (ref "U2") (pin "30") (pinfunction "PB11_30") (pintype "bidirectional+no_connect"))
    )
    (net (code "70") (name "unconnected-(U2-PB12-Pad33)") (class "Default")
      (node (ref "U2") (pin "33") (pinfunction "PB12_33") (pintype "bidirectional+no_connect"))
    )
    (net (code "71") (name "unconnected-(U2-PB13-Pad34)") (class "Default")
      (node (ref "U2") (pin "34") (pinfunction "PB13_34") (pintype "bidirectional+no_connect"))
    )
    (net (code "72") (name "unconnected-(U2-PB14-Pad35)") (class "Default")
      (node (ref "U2") (pin "35") (pinfunction "PB14_35") (pintype "bidirectional+no_connect"))
    )
    (net (code "73") (name "unconnected-(U2-PB15-Pad36)") (class "Default")
      (node (ref "U2") (pin "36") (pinfunction "PB15_36") (pintype "bidirectional+no_connect"))
    )
    (net (code "74") (name "unconnected-(U2-PC4-Pad24)") (class "Default")
      (node (ref "U2") (pin "24") (pinfunction "PC4_24") (pintype "bidirectional+no_connect"))
    )
    (net (code "75") (name "unconnected-(U2-PC5-Pad25)") (class "Default")
      (node (ref "U2") (pin "25") (pinfunction "PC5_25") (pintype "bidirectional+no_connect"))
    )
    (net (code "76") (name "unconnected-(U2-PC10-Pad51)") (class "Default")
      (node (ref "U2") (pin "51") (pinfunction "PC10_51") (pintype "bidirectional+no_connect"))
    )
    (net (code "77") (name "unconnected-(U2-PC11-Pad52)") (class "Default")
      (node (ref "U2") (pin "52") (pinfunction "PC11_52") (pintype "bidirectional+no_connect"))
    )
    (net (code "78") (name "unconnected-(U2-PC12-Pad53)") (class "Default")
      (node (ref "U2") (pin "53") (pinfunction "PC12_53") (pintype "bidirectional+no_connect"))
    )
    (net (code "79") (name "unconnected-(U2-PC14-OSC32_IN-Pad3)") (class "Default")
      (node (ref "U2") (pin "3") (pinfunction "PC14-OSC32_IN_3") (pintype "bidirectional+no_connect"))
    )
    (net (code "80") (name "unconnected-(U2-PC15-OSC32_OUT-Pad4)") (class "Default")
      (node (ref "U2") (pin "4") (pinfunction "PC15-OSC32_OUT_4") (pintype "bidirectional+no_connect"))
    )
    (net (code "81") (name "unconnected-(U2-PD2-Pad54)") (class "Default")
      (node (ref "U2") (pin "54") (pinfunction "PD2_54") (pintype "bidirectional+no_connect"))
    )
  )
)
